# KEX_V1.net
KiCad netlist of a schematic drawn in EAGLE
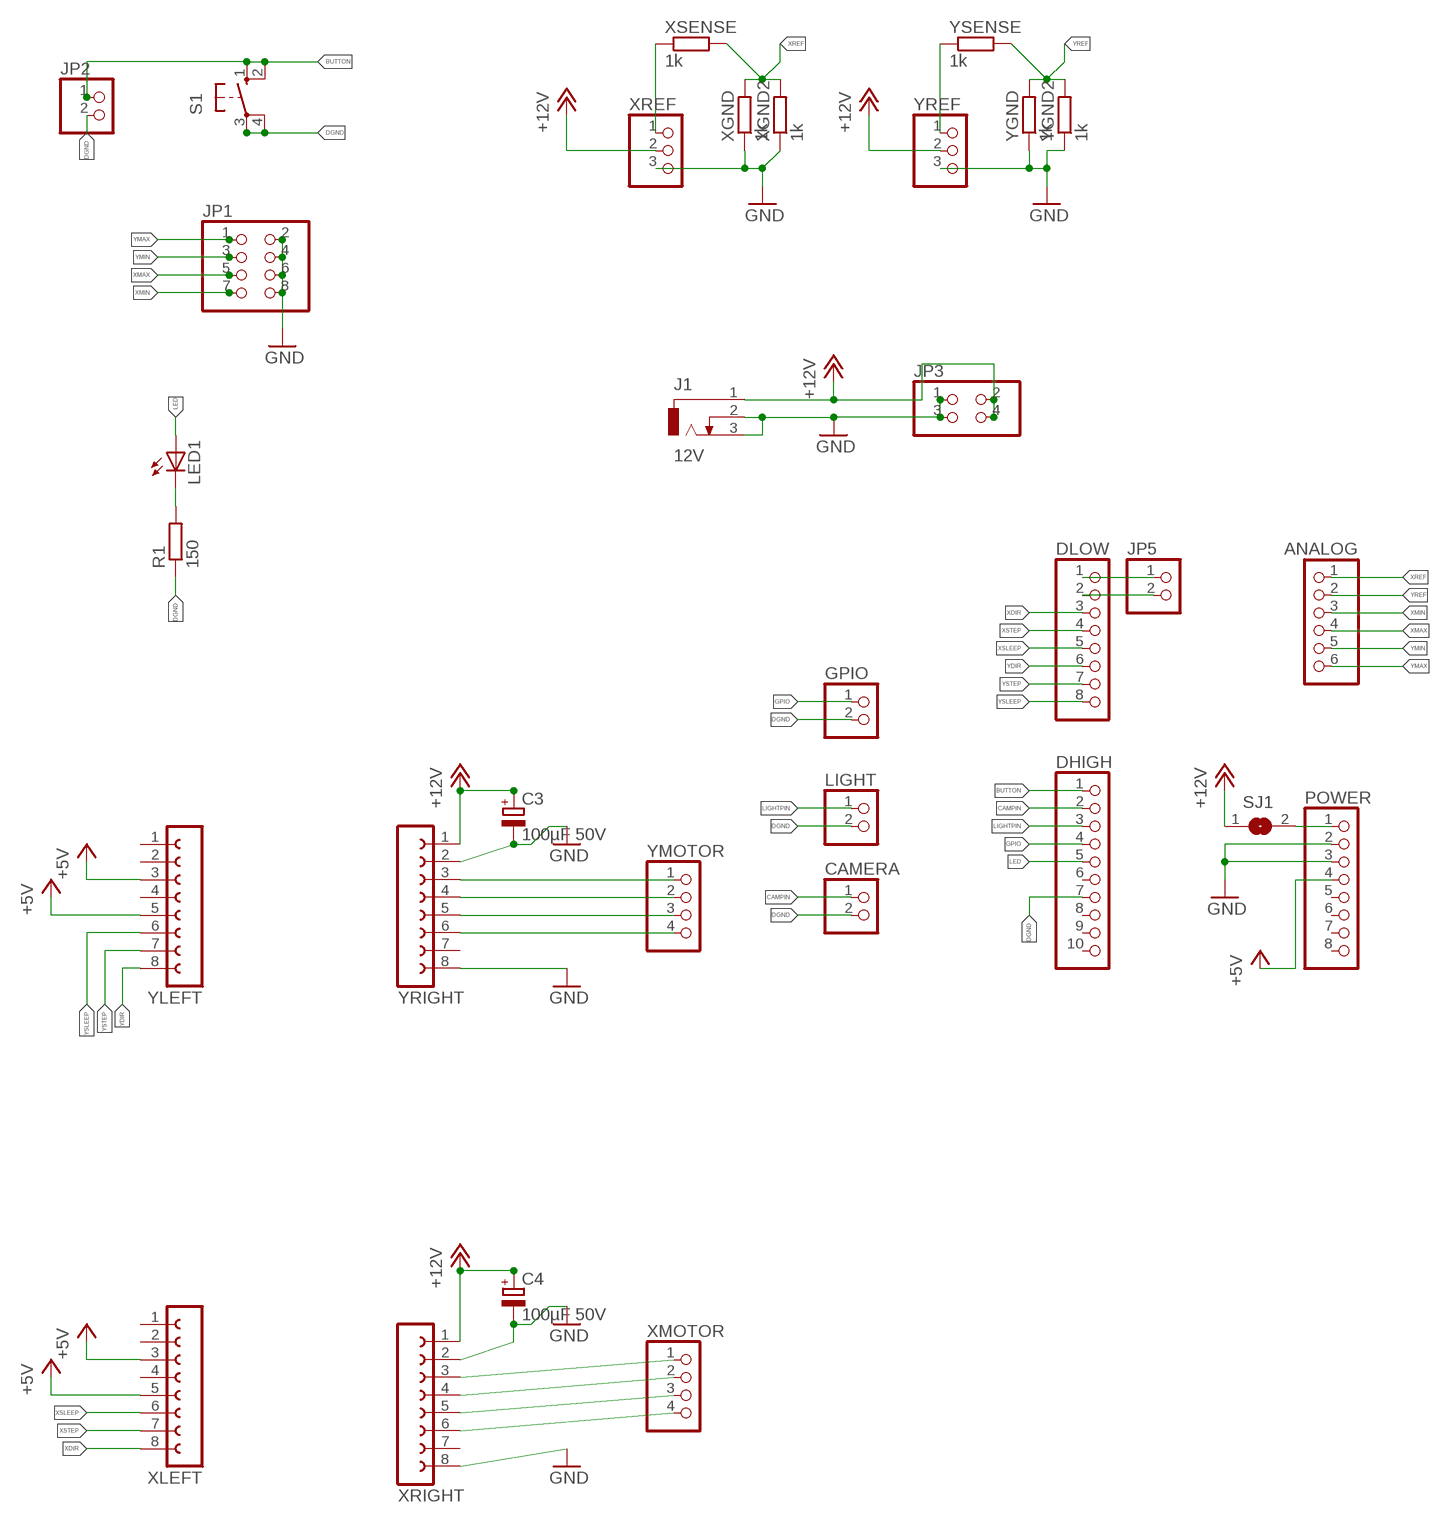
[diagram p0: schematic, sheet 1]

(export (version "E")
  (design (tool "Eeschema 10.0.6"))
  (components
    (comp (ref "ANALOG")
      (value "PINHD-1X6")
      (footprint "eagle-import:1X06")
      (libsource (lib "eagle-import") (part "PINHD-1X6"))
    )
    (comp (ref "C3")
      (value "100µF 50V")
      (footprint "eagle-import:E3,5-8")
      (libsource (lib "eagle-import") (part "CPOL-EUE3.5-8"))
    )
    (comp (ref "C4")
      (value "100µF 50V")
      (footprint "eagle-import:E3,5-8")
      (libsource (lib "eagle-import") (part "CPOL-EUE3.5-8"))
    )
    (comp (ref "CAMERA")
      (value "PINHD-1X2")
      (footprint "eagle-import:1X02")
      (libsource (lib "eagle-import") (part "PINHD-1X2"))
    )
    (comp (ref "DHIGH")
      (value "PINHD-1X10")
      (footprint "eagle-import:1X10")
      (libsource (lib "eagle-import") (part "PINHD-1X10"))
    )
    (comp (ref "DLOW")
      (value "PINHD-1X8")
      (footprint "eagle-import:1X08")
      (libsource (lib "eagle-import") (part "PINHD-1X8"))
    )
    (comp (ref "GPIO")
      (value "PINHD-1X2")
      (footprint "eagle-import:1X02")
      (libsource (lib "eagle-import") (part "PINHD-1X2"))
    )
    (comp (ref "J1")
      (value "12V")
      (footprint "eagle-import:DCJ0303")
      (libsource (lib "eagle-import") (part "DCJ0303"))
    )
    (comp (ref "JP1")
      (value "PINHD-2X4")
      (footprint "eagle-import:2X04")
      (libsource (lib "eagle-import") (part "PINHD-2X4"))
    )
    (comp (ref "JP2")
      (value "PINHD-1X2")
      (footprint "eagle-import:1X02")
      (libsource (lib "eagle-import") (part "PINHD-1X2"))
    )
    (comp (ref "JP3")
      (value "PINHD-2X2")
      (footprint "eagle-import:2X02")
      (libsource (lib "eagle-import") (part "PINHD-2X2"))
    )
    (comp (ref "JP5")
      (value "PINHD-1X2")
      (footprint "eagle-import:1X02")
      (libsource (lib "eagle-import") (part "PINHD-1X2"))
    )
    (comp (ref "LED1")
      (value "LED5MM")
      (footprint "eagle-import:LED5MM")
      (libsource (lib "eagle-import") (part "LED5MM"))
    )
    (comp (ref "LIGHT")
      (value "PINHD-1X2")
      (footprint "eagle-import:1X02")
      (libsource (lib "eagle-import") (part "PINHD-1X2"))
    )
    (comp (ref "POWER")
      (value "PINHD-1X8")
      (footprint "eagle-import:1X08")
      (libsource (lib "eagle-import") (part "PINHD-1X8"))
    )
    (comp (ref "R1")
      (value "150")
      (footprint "eagle-import:0204_7")
      (libsource (lib "eagle-import") (part "R-EU_0204/7"))
    )
    (comp (ref "S1")
      (value "10-XX")
      (footprint "eagle-import:B3F-10XX")
      (fields (field (name "MPN") "B3F-1000"))
      (libsource (lib "eagle-import") (part "10-XX"))
    )
    (comp (ref "SJ1") (value "SJ") (footprint "eagle-import:SJ") (libsource (lib "eagle-import") (part "SJ")))
    (comp (ref "XGND")
      (value "1k")
      (footprint "eagle-import:0204_7")
      (libsource (lib "eagle-import") (part "R-EU_0204/7"))
    )
    (comp (ref "XGND2")
      (value "1k")
      (footprint "eagle-import:0204_7")
      (libsource (lib "eagle-import") (part "R-EU_0204/7"))
    )
    (comp (ref "XLEFT")
      (value "FE08-1")
      (footprint "eagle-import:FE08")
      (libsource (lib "eagle-import") (part "FE08-1"))
    )
    (comp (ref "XMOTOR")
      (value "PINHD-1X4")
      (footprint "eagle-import:1X04")
      (libsource (lib "eagle-import") (part "PINHD-1X4"))
    )
    (comp (ref "XREF")
      (value "PINHD-1X3")
      (footprint "eagle-import:1X03")
      (libsource (lib "eagle-import") (part "PINHD-1X3"))
    )
    (comp (ref "XRIGHT")
      (value "FE08-1")
      (footprint "eagle-import:FE08")
      (libsource (lib "eagle-import") (part "FE08-1"))
    )
    (comp (ref "XSENSE")
      (value "1k")
      (footprint "eagle-import:0204_7")
      (libsource (lib "eagle-import") (part "R-EU_0204/7"))
    )
    (comp (ref "YGND")
      (value "1k")
      (footprint "eagle-import:0204_7")
      (libsource (lib "eagle-import") (part "R-EU_0204/7"))
    )
    (comp (ref "YGND2")
      (value "1k")
      (footprint "eagle-import:0204_7")
      (libsource (lib "eagle-import") (part "R-EU_0204/7"))
    )
    (comp (ref "YLEFT")
      (value "FE08-1")
      (footprint "eagle-import:FE08")
      (libsource (lib "eagle-import") (part "FE08-1"))
    )
    (comp (ref "YMOTOR")
      (value "PINHD-1X4")
      (footprint "eagle-import:1X04")
      (libsource (lib "eagle-import") (part "PINHD-1X4"))
    )
    (comp (ref "YREF")
      (value "PINHD-1X3")
      (footprint "eagle-import:1X03")
      (libsource (lib "eagle-import") (part "PINHD-1X3"))
    )
    (comp (ref "YRIGHT")
      (value "FE08-1")
      (footprint "eagle-import:FE08")
      (libsource (lib "eagle-import") (part "FE08-1"))
    )
    (comp (ref "YSENSE")
      (value "1k")
      (footprint "eagle-import:0204_7")
      (libsource (lib "eagle-import") (part "R-EU_0204/7"))
    )
  )
  (nets
    (net (code "1") (name "+5V") (class "Default")
      (node (ref "POWER") (pin "4") (pinfunction "4_4") (pintype "passive"))
      (node (ref "XLEFT") (pin "3") (pinfunction "3_3") (pintype "passive"))
      (node (ref "XLEFT") (pin "5") (pinfunction "5_5") (pintype "passive"))
      (node (ref "YLEFT") (pin "3") (pinfunction "3_3") (pintype "passive"))
      (node (ref "YLEFT") (pin "5") (pinfunction "5_5") (pintype "passive"))
    )
    (net (code "2") (name "+12V") (class "Default")
      (node (ref "C3") (pin "+") (pinfunction "+_+") (pintype "passive"))
      (node (ref "C4") (pin "+") (pinfunction "+_+") (pintype "passive"))
      (node (ref "J1") (pin "1") (pinfunction "1_1") (pintype "passive"))
      (node (ref "JP3") (pin "2") (pinfunction "2_2") (pintype "passive"))
      (node (ref "JP3") (pin "4") (pinfunction "4_4") (pintype "passive"))
      (node (ref "SJ1") (pin "1") (pinfunction "1_1") (pintype "passive"))
      (node (ref "XREF") (pin "2") (pinfunction "2_2") (pintype "passive"))
      (node (ref "XRIGHT") (pin "1") (pinfunction "1_1") (pintype "passive"))
      (node (ref "YREF") (pin "2") (pinfunction "2_2") (pintype "passive"))
      (node (ref "YRIGHT") (pin "1") (pinfunction "1_1") (pintype "passive"))
    )
    (net (code "3") (name "BUTTON") (class "Default")
      (node (ref "DHIGH") (pin "1") (pinfunction "1_1") (pintype "passive"))
      (node (ref "JP2") (pin "1") (pinfunction "1_1") (pintype "passive"))
      (node (ref "S1") (pin "1") (pinfunction "S_1") (pintype "passive"))
      (node (ref "S1") (pin "2") (pinfunction "S1_2") (pintype "passive"))
    )
    (net (code "4") (name "CAMPIN") (class "Default")
      (node (ref "CAMERA") (pin "1") (pinfunction "1_1") (pintype "passive"))
      (node (ref "DHIGH") (pin "2") (pinfunction "2_2") (pintype "passive"))
    )
    (net (code "5") (name "DGND") (class "Default")
      (node (ref "CAMERA") (pin "2") (pinfunction "2_2") (pintype "passive"))
      (node (ref "DHIGH") (pin "7") (pinfunction "7_7") (pintype "passive"))
      (node (ref "GPIO") (pin "2") (pinfunction "2_2") (pintype "passive"))
      (node (ref "JP2") (pin "2") (pinfunction "2_2") (pintype "passive"))
      (node (ref "LIGHT") (pin "2") (pinfunction "2_2") (pintype "passive"))
      (node (ref "R1") (pin "1") (pinfunction "1_1") (pintype "passive"))
      (node (ref "S1") (pin "3") (pinfunction "P_3") (pintype "passive"))
      (node (ref "S1") (pin "4") (pinfunction "P1_4") (pintype "passive"))
    )
    (net (code "6") (name "GND") (class "Default")
      (node (ref "C3") (pin "-") (pinfunction "-_-") (pintype "passive"))
      (node (ref "C4") (pin "-") (pinfunction "-_-") (pintype "passive"))
      (node (ref "J1") (pin "2") (pinfunction "2_2") (pintype "passive"))
      (node (ref "J1") (pin "3") (pinfunction "3_3") (pintype "passive"))
      (node (ref "JP1") (pin "2") (pinfunction "2_2") (pintype "passive"))
      (node (ref "JP1") (pin "4") (pinfunction "4_4") (pintype "passive"))
      (node (ref "JP1") (pin "6") (pinfunction "6_6") (pintype "passive"))
      (node (ref "JP1") (pin "8") (pinfunction "8_8") (pintype "passive"))
      (node (ref "JP3") (pin "1") (pinfunction "1_1") (pintype "passive"))
      (node (ref "JP3") (pin "3") (pinfunction "3_3") (pintype "passive"))
      (node (ref "POWER") (pin "2") (pinfunction "2_2") (pintype "passive"))
      (node (ref "POWER") (pin "3") (pinfunction "3_3") (pintype "passive"))
      (node (ref "XGND") (pin "1") (pinfunction "1_1") (pintype "passive"))
      (node (ref "XGND2") (pin "1") (pinfunction "1_1") (pintype "passive"))
      (node (ref "XREF") (pin "3") (pinfunction "3_3") (pintype "passive"))
      (node (ref "XRIGHT") (pin "2") (pinfunction "2_2") (pintype "passive"))
      (node (ref "XRIGHT") (pin "8") (pinfunction "8_8") (pintype "passive"))
      (node (ref "YGND") (pin "1") (pinfunction "1_1") (pintype "passive"))
      (node (ref "YGND2") (pin "1") (pinfunction "1_1") (pintype "passive"))
      (node (ref "YREF") (pin "3") (pinfunction "3_3") (pintype "passive"))
      (node (ref "YRIGHT") (pin "2") (pinfunction "2_2") (pintype "passive"))
      (node (ref "YRIGHT") (pin "8") (pinfunction "8_8") (pintype "passive"))
    )
    (net (code "7") (name "GPIO") (class "Default")
      (node (ref "DHIGH") (pin "4") (pinfunction "4_4") (pintype "passive"))
      (node (ref "GPIO") (pin "1") (pinfunction "1_1") (pintype "passive"))
    )
    (net (code "8") (name "LED") (class "Default")
      (node (ref "DHIGH") (pin "5") (pinfunction "5_5") (pintype "passive"))
      (node (ref "LED1") (pin "A") (pinfunction "A_A") (pintype "passive"))
    )
    (net (code "9") (name "LIGHTPIN") (class "Default")
      (node (ref "DHIGH") (pin "3") (pinfunction "3_3") (pintype "passive"))
      (node (ref "LIGHT") (pin "1") (pinfunction "1_1") (pintype "passive"))
    )
    (net (code "10") (name "Net-(DLOW-Pad1)") (class "Default")
      (node (ref "DLOW") (pin "1") (pinfunction "1_1") (pintype "passive"))
      (node (ref "JP5") (pin "1") (pinfunction "1_1") (pintype "passive"))
    )
    (net (code "11") (name "Net-(DLOW-Pad2)") (class "Default")
      (node (ref "DLOW") (pin "2") (pinfunction "2_2") (pintype "passive"))
      (node (ref "JP5") (pin "2") (pinfunction "2_2") (pintype "passive"))
    )
    (net (code "12") (name "Net-(LED1-C)") (class "Default")
      (node (ref "LED1") (pin "K") (pinfunction "C_K") (pintype "passive"))
      (node (ref "R1") (pin "2") (pinfunction "2_2") (pintype "passive"))
    )
    (net (code "13") (name "Net-(POWER-Pad1)") (class "Default")
      (node (ref "POWER") (pin "1") (pinfunction "1_1") (pintype "passive"))
      (node (ref "SJ1") (pin "2") (pinfunction "2_2") (pintype "passive"))
    )
    (net (code "14") (name "Net-(XMOTOR-Pad1)") (class "Default")
      (node (ref "XMOTOR") (pin "1") (pinfunction "1_1") (pintype "passive"))
      (node (ref "XRIGHT") (pin "3") (pinfunction "3_3") (pintype "passive"))
    )
    (net (code "15") (name "Net-(XMOTOR-Pad2)") (class "Default")
      (node (ref "XMOTOR") (pin "2") (pinfunction "2_2") (pintype "passive"))
      (node (ref "XRIGHT") (pin "4") (pinfunction "4_4") (pintype "passive"))
    )
    (net (code "16") (name "Net-(XMOTOR-Pad3)") (class "Default")
      (node (ref "XMOTOR") (pin "3") (pinfunction "3_3") (pintype "passive"))
      (node (ref "XRIGHT") (pin "5") (pinfunction "5_5") (pintype "passive"))
    )
    (net (code "17") (name "Net-(XMOTOR-Pad4)") (class "Default")
      (node (ref "XMOTOR") (pin "4") (pinfunction "4_4") (pintype "passive"))
      (node (ref "XRIGHT") (pin "6") (pinfunction "6_6") (pintype "passive"))
    )
    (net (code "18") (name "Net-(XREF-Pad1)") (class "Default")
      (node (ref "XREF") (pin "1") (pinfunction "1_1") (pintype "passive"))
      (node (ref "XSENSE") (pin "1") (pinfunction "1_1") (pintype "passive"))
    )
    (net (code "19") (name "Net-(YMOTOR-Pad1)") (class "Default")
      (node (ref "YMOTOR") (pin "1") (pinfunction "1_1") (pintype "passive"))
      (node (ref "YRIGHT") (pin "3") (pinfunction "3_3") (pintype "passive"))
    )
    (net (code "20") (name "Net-(YMOTOR-Pad2)") (class "Default")
      (node (ref "YMOTOR") (pin "2") (pinfunction "2_2") (pintype "passive"))
      (node (ref "YRIGHT") (pin "4") (pinfunction "4_4") (pintype "passive"))
    )
    (net (code "21") (name "Net-(YMOTOR-Pad3)") (class "Default")
      (node (ref "YMOTOR") (pin "3") (pinfunction "3_3") (pintype "passive"))
      (node (ref "YRIGHT") (pin "5") (pinfunction "5_5") (pintype "passive"))
    )
    (net (code "22") (name "Net-(YMOTOR-Pad4)") (class "Default")
      (node (ref "YMOTOR") (pin "4") (pinfunction "4_4") (pintype "passive"))
      (node (ref "YRIGHT") (pin "6") (pinfunction "6_6") (pintype "passive"))
    )
    (net (code "23") (name "Net-(YREF-Pad1)") (class "Default")
      (node (ref "YREF") (pin "1") (pinfunction "1_1") (pintype "passive"))
      (node (ref "YSENSE") (pin "1") (pinfunction "1_1") (pintype "passive"))
    )
    (net (code "24") (name "XDIR") (class "Default")
      (node (ref "DLOW") (pin "3") (pinfunction "3_3") (pintype "passive"))
      (node (ref "XLEFT") (pin "8") (pinfunction "8_8") (pintype "passive"))
    )
    (net (code "25") (name "XMAX") (class "Default")
      (node (ref "ANALOG") (pin "4") (pinfunction "4_4") (pintype "passive"))
      (node (ref "JP1") (pin "5") (pinfunction "5_5") (pintype "passive"))
    )
    (net (code "26") (name "XMIN") (class "Default")
      (node (ref "ANALOG") (pin "3") (pinfunction "3_3") (pintype "passive"))
      (node (ref "JP1") (pin "7") (pinfunction "7_7") (pintype "passive"))
    )
    (net (code "27") (name "XREF") (class "Default")
      (node (ref "ANALOG") (pin "1") (pinfunction "1_1") (pintype "passive"))
      (node (ref "XGND") (pin "2") (pinfunction "2_2") (pintype "passive"))
      (node (ref "XGND2") (pin "2") (pinfunction "2_2") (pintype "passive"))
      (node (ref "XSENSE") (pin "2") (pinfunction "2_2") (pintype "passive"))
    )
    (net (code "28") (name "XSLEEP") (class "Default")
      (node (ref "DLOW") (pin "5") (pinfunction "5_5") (pintype "passive"))
      (node (ref "XLEFT") (pin "6") (pinfunction "6_6") (pintype "passive"))
    )
    (net (code "29") (name "XSTEP") (class "Default")
      (node (ref "DLOW") (pin "4") (pinfunction "4_4") (pintype "passive"))
      (node (ref "XLEFT") (pin "7") (pinfunction "7_7") (pintype "passive"))
    )
    (net (code "30") (name "YDIR") (class "Default")
      (node (ref "DLOW") (pin "6") (pinfunction "6_6") (pintype "passive"))
      (node (ref "YLEFT") (pin "8") (pinfunction "8_8") (pintype "passive"))
    )
    (net (code "31") (name "YMAX") (class "Default")
      (node (ref "ANALOG") (pin "6") (pinfunction "6_6") (pintype "passive"))
      (node (ref "JP1") (pin "1") (pinfunction "1_1") (pintype "passive"))
    )
    (net (code "32") (name "YMIN") (class "Default")
      (node (ref "ANALOG") (pin "5") (pinfunction "5_5") (pintype "passive"))
      (node (ref "JP1") (pin "3") (pinfunction "3_3") (pintype "passive"))
    )
    (net (code "33") (name "YREF") (class "Default")
      (node (ref "ANALOG") (pin "2") (pinfunction "2_2") (pintype "passive"))
      (node (ref "YGND") (pin "2") (pinfunction "2_2") (pintype "passive"))
      (node (ref "YGND2") (pin "2") (pinfunction "2_2") (pintype "passive"))
      (node (ref "YSENSE") (pin "2") (pinfunction "2_2") (pintype "passive"))
    )
    (net (code "34") (name "YSLEEP") (class "Default")
      (node (ref "DLOW") (pin "8") (pinfunction "8_8") (pintype "passive"))
      (node (ref "YLEFT") (pin "6") (pinfunction "6_6") (pintype "passive"))
    )
    (net (code "35") (name "YSTEP") (class "Default")
      (node (ref "DLOW") (pin "7") (pinfunction "7_7") (pintype "passive"))
      (node (ref "YLEFT") (pin "7") (pinfunction "7_7") (pintype "passive"))
    )
    (net (code "36") (name "unconnected-(DHIGH-Pad6)") (class "Default")
      (node (ref "DHIGH") (pin "6") (pinfunction "6_6") (pintype "passive"))
    )
    (net (code "37") (name "unconnected-(DHIGH-Pad8)") (class "Default")
      (node (ref "DHIGH") (pin "8") (pinfunction "8_8") (pintype "passive"))
    )
    (net (code "38") (name "unconnected-(DHIGH-Pad9)") (class "Default")
      (node (ref "DHIGH") (pin "9") (pinfunction "9_9") (pintype "passive"))
    )
    (net (code "39") (name "unconnected-(DHIGH-Pad10)") (class "Default")
      (node (ref "DHIGH") (pin "10") (pinfunction "10_10") (pintype "passive"))
    )
    (net (code "40") (name "unconnected-(POWER-Pad5)") (class "Default")
      (node (ref "POWER") (pin "5") (pinfunction "5_5") (pintype "passive"))
    )
    (net (code "41") (name "unconnected-(POWER-Pad6)") (class "Default")
      (node (ref "POWER") (pin "6") (pinfunction "6_6") (pintype "passive"))
    )
    (net (code "42") (name "unconnected-(POWER-Pad7)") (class "Default")
      (node (ref "POWER") (pin "7") (pinfunction "7_7") (pintype "passive"))
    )
    (net (code "43") (name "unconnected-(POWER-Pad8)") (class "Default")
      (node (ref "POWER") (pin "8") (pinfunction "8_8") (pintype "passive"))
    )
    (net (code "44") (name "unconnected-(XLEFT-Pad1)") (class "Default")
      (node (ref "XLEFT") (pin "1") (pinfunction "1_1") (pintype "passive"))
    )
    (net (code "45") (name "unconnected-(XLEFT-Pad2)") (class "Default")
      (node (ref "XLEFT") (pin "2") (pinfunction "2_2") (pintype "passive"))
    )
    (net (code "46") (name "unconnected-(XLEFT-Pad4)") (class "Default")
      (node (ref "XLEFT") (pin "4") (pinfunction "4_4") (pintype "passive"))
    )
    (net (code "47") (name "unconnected-(XRIGHT-Pad7)") (class "Default")
      (node (ref "XRIGHT") (pin "7") (pinfunction "7_7") (pintype "passive"))
    )
    (net (code "48") (name "unconnected-(YLEFT-Pad1)") (class "Default")
      (node (ref "YLEFT") (pin "1") (pinfunction "1_1") (pintype "passive"))
    )
    (net (code "49") (name "unconnected-(YLEFT-Pad2)") (class "Default")
      (node (ref "YLEFT") (pin "2") (pinfunction "2_2") (pintype "passive"))
    )
    (net (code "50") (name "unconnected-(YLEFT-Pad4)") (class "Default")
      (node (ref "YLEFT") (pin "4") (pinfunction "4_4") (pintype "passive"))
    )
    (net (code "51") (name "unconnected-(YRIGHT-Pad7)") (class "Default")
      (node (ref "YRIGHT") (pin "7") (pinfunction "7_7") (pintype "passive"))
    )
  )
)
